# OpenVLC_1_3_2.net
KiCad netlist of a schematic drawn in Altium Designer
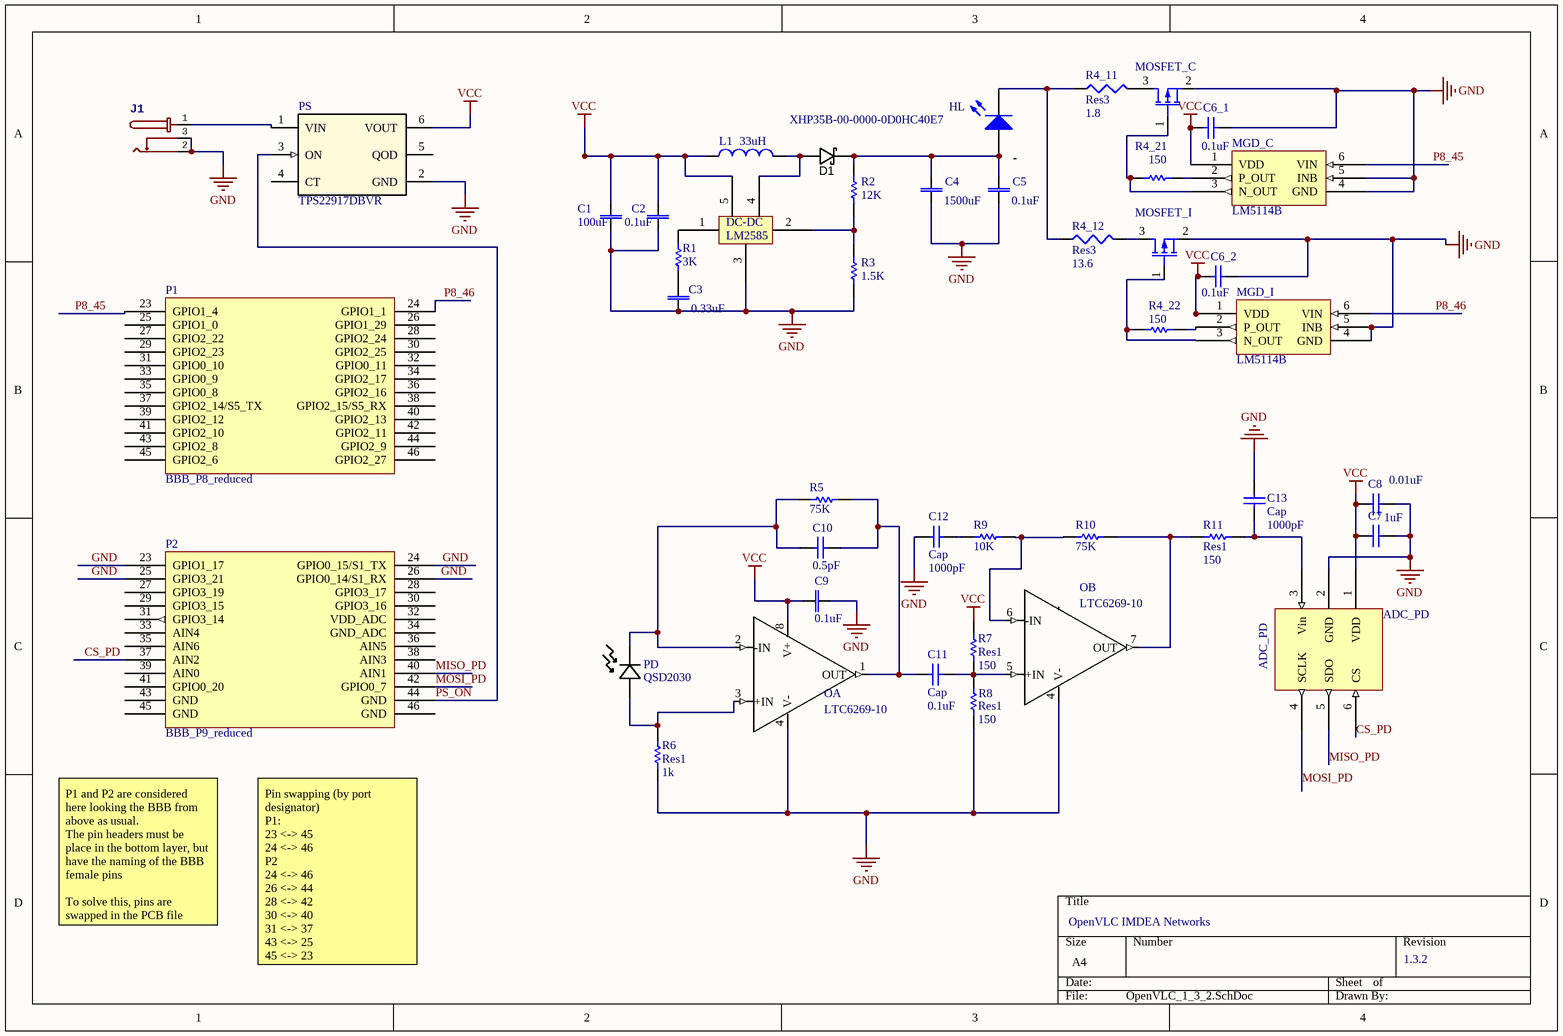
[diagram p0: OpenVLC_1_3_2.SchDoc]

(export (version "E")
  (design (tool "Eeschema 10.0.6"))
  (components
    (comp (ref "ADC_PD")
      (value "ADC_PD")
      (footprint "SOT23-6")
      (libsource (lib "BeagleBoneCape") (part "ADS7883"))
    )
    (comp (ref "C1")
      (value "100uF")
      (footprint "WCAP-ATG8 6.3x11x2.5x0.5")
      (description "Capacitor")
      (fields (field (name "Comment") "Cap") (field (name "PUBLISHER") "Altium Limited"))
      (libsource (lib "") (part "Cap_1"))
    )
    (comp (ref "C2")
      (value "0.1uF")
      (footprint "1608[0603]")
      (description "Capacitor")
      (fields (field (name "Comment") "Cap") (field (name "PUBLISHER") "Altium Limited"))
      (libsource (lib "") (part "Cap_1"))
    )
    (comp (ref "C3")
      (value "0.33uF")
      (footprint "1608[0603]")
      (description "Capacitor")
      (fields (field (name "Comment") "Cap") (field (name "PUBLISHER") "Altium Limited"))
      (libsource (lib "") (part "Cap_1"))
    )
    (comp (ref "C4")
      (value "1500uF")
      (footprint "WCAP-ATG8 10x12.5x5x0.6")
      (description "Capacitor")
      (fields (field (name "Comment") "Cap") (field (name "PUBLISHER") "Altium Limited"))
      (libsource (lib "") (part "Cap_1"))
    )
    (comp (ref "C5")
      (value "0.1uF")
      (footprint "1608[0603]")
      (description "Capacitor")
      (fields (field (name "Comment") "Cap") (field (name "PUBLISHER") "Altium Limited"))
      (libsource (lib "") (part "Cap_1"))
    )
    (comp (ref "C6_1")
      (value "0.1uF")
      (footprint "1608[0603]")
      (description "Capacitor")
      (fields (field (name "Comment") "Cap") (field (name "PUBLISHER") "Altium Limited"))
      (libsource (lib "Miscellaneous Devices") (part "Cap"))
    )
    (comp (ref "C6_2")
      (value "0.1uF")
      (footprint "1608[0603]")
      (description "Capacitor")
      (fields (field (name "Comment") "Cap") (field (name "PUBLISHER") "Altium Limited"))
      (libsource (lib "Miscellaneous Devices") (part "Cap"))
    )
    (comp (ref "C7")
      (value "1uF")
      (footprint "1608[0603]")
      (description "Capacitor")
      (fields (field (name "Comment") "Cap") (field (name "PUBLISHER") "Altium Limited"))
      (libsource (lib "Miscellaneous Devices") (part "Cap"))
    )
    (comp (ref "C8")
      (value "0.01uF")
      (footprint "1608[0603]")
      (description "Capacitor")
      (fields (field (name "Comment") "Cap") (field (name "PUBLISHER") "Altium Limited"))
      (libsource (lib "Miscellaneous Devices") (part "Cap"))
    )
    (comp (ref "C9")
      (value "0.1uF")
      (footprint "1608[0603]")
      (description "Capacitor")
      (fields (field (name "Comment") "Cap") (field (name "PUBLISHER") "Altium Limited"))
      (libsource (lib "BeagleBoneCape") (part "Cap"))
    )
    (comp (ref "C10")
      (value "0.5pF")
      (footprint "1608[0603]")
      (description "Capacitor")
      (fields (field (name "Comment") "Cap") (field (name "PUBLISHER") "Altium Limited"))
      (libsource (lib "Miscellaneous Devices") (part "Cap"))
    )
    (comp (ref "C11")
      (value "Cap")
      (footprint "1608[0603]")
      (description "Capacitor")
      (fields (field (name "ALTIUM_VALUE") "0.1uF") (field (name "PUBLISHER") "Altium Limited"))
      (libsource (lib "Miscellaneous Devices") (part "Cap"))
    )
    (comp (ref "C12")
      (value "Cap")
      (footprint "1608[0603]")
      (description "Capacitor")
      (fields (field (name "ALTIUM_VALUE") "1000pF") (field (name "PUBLISHER") "Altium Limited"))
      (libsource (lib "Miscellaneous Devices") (part "Cap"))
    )
    (comp (ref "C13")
      (value "Cap")
      (footprint "1608[0603]")
      (description "Capacitor")
      (fields (field (name "ALTIUM_VALUE") "1000pF") (field (name "PUBLISHER") "Altium Limited"))
      (libsource (lib "Miscellaneous Devices") (part "Cap"))
    )
    (comp (ref "D1")
      (value "~")
      (footprint "DO-214AC")
      (description "Diode Schottky SMD 100V 2A SMA")
      (libsource (lib "PBL - Diodes") (part "DIODE_SCHOTTKY_10MQ100NPBF"))
    )
    (comp (ref "DC-DC")
      (value "LM2585")
      (footprint "TO-263-5")
      (libsource (lib "BeagleBoneCape") (part "LM2585"))
    )
    (comp (ref "HL")
      (value "XHP35B-00-0000-0D0HC40E7")
      (footprint "LEDM345X345X226:LEDM345X345X226")
      (fields (field (name "PUBLISHER") "Altium Limited"))
      (libsource (lib "Miscellaneous Devices") (part "LED1"))
    )
    (comp (ref "J1")
      (value "2.0 mm Center Pin, 2.5 A, Right Angle, Through Hole, Tapered Pins, Dc Power Jack Connector")
      (footprint "CUI_PJ-102A")
      (fields (field (name "MF") "CUI") (field (name "MP") "PJ-102A"))
      (libsource (lib "PJ-102A") (part "PJ-102A"))
    )
    (comp (ref "L1")
      (value "33uH")
      (footprint "WCAP-ATG8:WCAP-ATG8 8x16x5x0.5")
      (description "Inductor")
      (fields (field (name "PUBLISHER") "Altium Limited"))
      (libsource (lib "Miscellaneous Devices") (part "Inductor"))
    )
    (comp (ref "MGD_C")
      (value "LM5114B")
      (footprint "SOT23-6_N")
      (description "MOSFET Gate Driver")
      (libsource (lib "BeagleBoneCape") (part "LM5114B"))
    )
    (comp (ref "MGD_I")
      (value "LM5114B")
      (footprint "SOT23-6_N")
      (description "MOSFET Gate Driver")
      (libsource (lib "BeagleBoneCape") (part "LM5114B"))
    )
    (comp (ref "MOSFET_C")
      (value "MOSFET")
      (footprint "SOT23-3")
      (description "P-Channel MOSFET")
      (fields (field (name "PUBLISHER") "Altium Limited"))
      (libsource (lib "Miscellaneous Devices") (part "MOSFET-P"))
    )
    (comp (ref "MOSFET_I")
      (value "MOSFET")
      (footprint "SOT23-3")
      (description "P-Channel MOSFET")
      (fields (field (name "PUBLISHER") "Altium Limited"))
      (libsource (lib "Miscellaneous Devices") (part "MOSFET-P"))
    )
    (comp (ref "O") (value "LTC6269-10") (footprint "SM8") (libsource (lib "") (part "LTC6269-10_1")))
    (comp (ref "P1")
      (value "BBB_P8_reduced")
      (footprint "BBB_CAPE_NO_HEADER_R_24")
      (libsource (lib "BeagleBoneCape") (part "BBB_P8_reduced"))
    )
    (comp (ref "P2")
      (value "BBB_P9_reduced")
      (footprint "BBB_CAPE_NO_HEADER_R_24")
      (libsource (lib "BeagleBoneCape") (part "BBB_P9_reduced"))
    )
    (comp (ref "PD")
      (value "QSD2030")
      (footprint "LED_T-1_34_100CF_OSI")
      (description "No Description Available")
      (libsource (lib "OpenVLC_1_3_2_SchLibrary") (part "QSD2030"))
    )
    (comp (ref "PS")
      (value "TPS22917DBVR")
      (footprint "DBV0006_N")
      (description "Power Switch 1.7-5.5V")
      (libsource (lib "Multi_OpenVLC_SchLibrary") (part "TPS22917DBVR"))
    )
    (comp (ref "R1")
      (value "3K")
      (footprint "1608[0603]")
      (description "Semiconductor Resistor")
      (fields (field (name "Comment") "Res Semi") (field (name "PUBLISHER") "Altium Limited"))
      (libsource (lib "Miscellaneous Devices") (part "Res Semi"))
    )
    (comp (ref "R2")
      (value "12K")
      (footprint "1608[0603]")
      (description "Resistor")
      (fields (field (name "Comment") "Res1") (field (name "PUBLISHER") "Altium Limited"))
      (libsource (lib "Miscellaneous Devices") (part "Res1"))
    )
    (comp (ref "R3")
      (value "1.5K")
      (footprint "1608[0603]")
      (description "Resistor")
      (fields (field (name "Comment") "Res1") (field (name "PUBLISHER") "Altium Limited"))
      (libsource (lib "Miscellaneous Devices") (part "Res1"))
    )
    (comp (ref "R4_11")
      (value "Res3")
      (footprint "14-1210")
      (description "Resistor")
      (fields (field (name "ALTIUM_VALUE") "1.8") (field (name "PUBLISHER") "Altium Limited"))
      (libsource (lib "Miscellaneous Devices") (part "Res3"))
    )
    (comp (ref "R4_12")
      (value "Res3")
      (footprint "C1206")
      (description "Resistor")
      (fields (field (name "ALTIUM_VALUE") "13.6") (field (name "PUBLISHER") "Altium Limited"))
      (libsource (lib "Miscellaneous Devices") (part "Res3"))
    )
    (comp (ref "R4_21")
      (value "150")
      (footprint "1608[0603]")
      (description "Resistor")
      (fields (field (name "Comment") "Res1") (field (name "PUBLISHER") "Altium Limited"))
      (libsource (lib "Miscellaneous Devices") (part "Res1"))
    )
    (comp (ref "R4_22")
      (value "150")
      (footprint "1608[0603]")
      (description "Resistor")
      (fields (field (name "Comment") "Res1") (field (name "PUBLISHER") "Altium Limited"))
      (libsource (lib "Miscellaneous Devices") (part "Res1"))
    )
    (comp (ref "R5")
      (value "75K")
      (footprint "1608[0603]")
      (description "Resistor")
      (fields (field (name "Comment") "Res1") (field (name "PUBLISHER") "Altium Limited"))
      (libsource (lib "Miscellaneous Devices") (part "Res1"))
    )
    (comp (ref "R6")
      (value "Res1")
      (footprint "1608[0603]")
      (description "Resistor")
      (fields (field (name "ALTIUM_VALUE") "1k") (field (name "PUBLISHER") "Altium Limited"))
      (libsource (lib "Miscellaneous Devices") (part "Res1"))
    )
    (comp (ref "R7")
      (value "Res1")
      (footprint "Miscellaneous Devices:1608[0603]")
      (description "Resistor")
      (fields (field (name "ALTIUM_VALUE") "150") (field (name "PUBLISHER") "Altium Limited"))
      (libsource (lib "Miscellaneous Devices") (part "Res1"))
    )
    (comp (ref "R8")
      (value "Res1")
      (footprint "1608[0603]")
      (description "Resistor")
      (fields (field (name "ALTIUM_VALUE") "150") (field (name "PUBLISHER") "Altium Limited"))
      (libsource (lib "Miscellaneous Devices") (part "Res1"))
    )
    (comp (ref "R9")
      (value "10K")
      (footprint "1608[0603]")
      (description "Resistor")
      (fields (field (name "Comment") "Res1") (field (name "PUBLISHER") "Altium Limited"))
      (libsource (lib "Miscellaneous Devices") (part "Res1"))
    )
    (comp (ref "R10")
      (value "75K")
      (footprint "1608[0603]")
      (description "Resistor")
      (fields (field (name "Comment") "Res1") (field (name "PUBLISHER") "Altium Limited"))
      (libsource (lib "Miscellaneous Devices") (part "Res1"))
    )
    (comp (ref "R11")
      (value "Res1")
      (footprint "1608[0603]")
      (description "Resistor")
      (fields (field (name "ALTIUM_VALUE") "150") (field (name "PUBLISHER") "Altium Limited"))
      (libsource (lib "Miscellaneous Devices") (part "Res1"))
    )
  )
  (nets
    (net (code "1") (name "/CS_PD") (class "Default")
      (node (ref "ADC_PD") (pin "6") (pinfunction "CS_6") (pintype "input"))
      (node (ref "P2") (pin "37") (pinfunction "AIN2_37") (pintype "passive"))
    )
    (net (code "2") (name "/MISO_PD") (class "Default")
      (node (ref "ADC_PD") (pin "5") (pinfunction "SDO_5") (pintype "output"))
      (node (ref "P2") (pin "40") (pinfunction "AIN1_40") (pintype "passive"))
    )
    (net (code "3") (name "/MOSI_PD") (class "Default")
      (node (ref "ADC_PD") (pin "4") (pinfunction "SCLK_4") (pintype "output"))
      (node (ref "P2") (pin "42") (pinfunction "GPIO0_7_42") (pintype "passive"))
    )
    (net (code "4") (name "/P8_45") (class "Default")
      (node (ref "MGD_C") (pin "6") (pinfunction "VIN_6") (pintype "input"))
      (node (ref "P1") (pin "23") (pinfunction "GPIO1_4_23") (pintype "passive"))
    )
    (net (code "5") (name "/P8_46") (class "Default")
      (node (ref "MGD_I") (pin "6") (pinfunction "VIN_6") (pintype "input"))
      (node (ref "P1") (pin "24") (pinfunction "GPIO1_1_24") (pintype "passive"))
    )
    (net (code "6") (name "/PS_ON") (class "Default")
      (node (ref "P2") (pin "44") (pinfunction "GND_44") (pintype "passive"))
      (node (ref "PS") (pin "3") (pinfunction "ON_3") (pintype "input"))
    )
    (net (code "7") (name "GND") (class "Default")
      (node (ref "ADC_PD") (pin "2") (pinfunction "GND_2") (pintype "power_in"))
      (node (ref "C1") (pin "2") (pinfunction "2_2") (pintype "passive"))
      (node (ref "C12") (pin "1") (pinfunction "1_1") (pintype "passive"))
      (node (ref "C13") (pin "2") (pinfunction "2_2") (pintype "passive"))
      (node (ref "C2") (pin "2") (pinfunction "2_2") (pintype "passive"))
      (node (ref "C3") (pin "2") (pinfunction "2_2") (pintype "passive"))
      (node (ref "C4") (pin "2") (pinfunction "2_2") (pintype "passive"))
      (node (ref "C5") (pin "2") (pinfunction "2_2") (pintype "passive"))
      (node (ref "C6_1") (pin "2") (pinfunction "2_2") (pintype "passive"))
      (node (ref "C6_2") (pin "2") (pinfunction "2_2") (pintype "passive"))
      (node (ref "C7") (pin "2") (pinfunction "2_2") (pintype "passive"))
      (node (ref "C8") (pin "2") (pinfunction "2_2") (pintype "passive"))
      (node (ref "C9") (pin "1") (pinfunction "1_1") (pintype "passive"))
      (node (ref "DC-DC") (pin "3") (pinfunction "GND_3") (pintype "passive"))
      (node (ref "J1") (pin "2") (pinfunction "2_2") (pintype "power_in"))
      (node (ref "J1") (pin "3") (pinfunction "3_3") (pintype "power_in"))
      (node (ref "MGD_C") (pin "4") (pinfunction "GND_4") (pintype "power_in"))
      (node (ref "MGD_C") (pin "5") (pinfunction "INB_5") (pintype "input"))
      (node (ref "MGD_I") (pin "4") (pinfunction "GND_4") (pintype "power_in"))
      (node (ref "MGD_I") (pin "5") (pinfunction "INB_5") (pintype "input"))
      (node (ref "MOSFET_C") (pin "2") (pinfunction "S_2") (pintype "passive"))
      (node (ref "MOSFET_I") (pin "2") (pinfunction "S_2") (pintype "passive"))
      (node (ref "O") (pin "4") (pinfunction "V-_4") (pintype "power_in"))
      (node (ref "P2") (pin "23") (pinfunction "GPIO1_17_23") (pintype "passive"))
      (node (ref "P2") (pin "24") (pinfunction "GPIO0_15/S1_TX_24") (pintype "passive"))
      (node (ref "P2") (pin "25") (pinfunction "GPIO3_21_25") (pintype "passive"))
      (node (ref "P2") (pin "26") (pinfunction "GPIO0_14/S1_RX_26") (pintype "passive"))
      (node (ref "PS") (pin "2") (pinfunction "GND_2") (pintype "power_in"))
      (node (ref "R3") (pin "1") (pinfunction "1_1") (pintype "passive"))
      (node (ref "R6") (pin "1") (pinfunction "1_1") (pintype "passive"))
      (node (ref "R8") (pin "1") (pinfunction "1_1") (pintype "passive"))
    )
    (net (code "8") (name "Net-(ADC_PD-Vin)") (class "Default")
      (node (ref "ADC_PD") (pin "3") (pinfunction "Vin_3") (pintype "input"))
      (node (ref "C13") (pin "1") (pinfunction "1_1") (pintype "passive"))
      (node (ref "R11") (pin "1") (pinfunction "1_1") (pintype "passive"))
    )
    (net (code "9") (name "Net-(C3-Pad1)") (class "Default")
      (node (ref "C3") (pin "1") (pinfunction "1_1") (pintype "passive"))
      (node (ref "R1") (pin "1") (pinfunction "1_1") (pintype "passive"))
    )
    (net (code "10") (name "Net-(C12-Pad2)") (class "Default")
      (node (ref "C12") (pin "2") (pinfunction "2_2") (pintype "passive"))
      (node (ref "R9") (pin "2") (pinfunction "2_2") (pintype "passive"))
    )
    (net (code "11") (name "Net-(DC-DC-Comp)") (class "Default")
      (node (ref "DC-DC") (pin "1") (pinfunction "Comp_1") (pintype "passive"))
      (node (ref "R1") (pin "2") (pinfunction "2_2") (pintype "passive"))
    )
    (net (code "12") (name "Net-(DC-DC-Feedack)") (class "Default")
      (node (ref "DC-DC") (pin "2") (pinfunction "Feedack_2") (pintype "passive"))
      (node (ref "R2") (pin "1") (pinfunction "1_1") (pintype "passive"))
      (node (ref "R3") (pin "2") (pinfunction "2_2") (pintype "passive"))
    )
    (net (code "13") (name "Net-(DC-DC-Switch)") (class "Default")
      (node (ref "D1") (pin "A") (pinfunction "A_A") (pintype "passive"))
      (node (ref "DC-DC") (pin "4") (pinfunction "Switch_4") (pintype "passive"))
      (node (ref "L1") (pin "2") (pinfunction "2_2") (pintype "passive"))
    )
    (net (code "14") (name "Net-(HL-A)") (class "Default")
      (node (ref "C4") (pin "1") (pinfunction "1_1") (pintype "passive"))
      (node (ref "C5") (pin "1") (pinfunction "1_1") (pintype "passive"))
      (node (ref "D1") (pin "K") (pinfunction "K_K") (pintype "passive"))
      (node (ref "HL") (pin "1") (pinfunction "A_1") (pintype "passive"))
      (node (ref "R2") (pin "2") (pinfunction "2_2") (pintype "passive"))
    )
    (net (code "15") (name "Net-(HL-K)") (class "Default")
      (node (ref "HL") (pin "2") (pinfunction "K_2") (pintype "passive"))
      (node (ref "R4_11") (pin "1") (pinfunction "1_1") (pintype "passive"))
      (node (ref "R4_12") (pin "1") (pinfunction "1_1") (pintype "passive"))
    )
    (net (code "16") (name "Net-(MGD_C-N_OUT)") (class "Default")
      (node (ref "MGD_C") (pin "3") (pinfunction "N_OUT_3") (pintype "output"))
      (node (ref "MOSFET_C") (pin "1") (pinfunction "G_1") (pintype "passive"))
      (node (ref "R4_21") (pin "1") (pinfunction "1_1") (pintype "passive"))
    )
    (net (code "17") (name "Net-(MGD_C-P_OUT)") (class "Default")
      (node (ref "MGD_C") (pin "2") (pinfunction "P_OUT_2") (pintype "output"))
      (node (ref "R4_21") (pin "2") (pinfunction "2_2") (pintype "passive"))
    )
    (net (code "18") (name "Net-(MGD_I-N_OUT)") (class "Default")
      (node (ref "MGD_I") (pin "3") (pinfunction "N_OUT_3") (pintype "output"))
      (node (ref "MOSFET_I") (pin "1") (pinfunction "G_1") (pintype "passive"))
      (node (ref "R4_22") (pin "1") (pinfunction "1_1") (pintype "passive"))
    )
    (net (code "19") (name "Net-(MGD_I-P_OUT)") (class "Default")
      (node (ref "MGD_I") (pin "2") (pinfunction "P_OUT_2") (pintype "output"))
      (node (ref "R4_22") (pin "2") (pinfunction "2_2") (pintype "passive"))
    )
    (net (code "20") (name "Net-(MOSFET_C-D)") (class "Default")
      (node (ref "MOSFET_C") (pin "3") (pinfunction "D_3") (pintype "passive"))
      (node (ref "R4_11") (pin "2") (pinfunction "2_2") (pintype "passive"))
    )
    (net (code "21") (name "Net-(MOSFET_I-D)") (class "Default")
      (node (ref "MOSFET_I") (pin "3") (pinfunction "D_3") (pintype "passive"))
      (node (ref "R4_12") (pin "2") (pinfunction "2_2") (pintype "passive"))
    )
    (net (code "22") (name "Net-(OA-+IN)") (class "Default")
      (node (ref "O") (pin "3") (pinfunction "+IN_3") (pintype "input"))
      (node (ref "PD") (pin "2") (pinfunction "ANODE_2") (pintype "passive"))
      (node (ref "R6") (pin "2") (pinfunction "2_2") (pintype "passive"))
    )
    (net (code "23") (name "Net-(OA--IN)") (class "Default")
      (node (ref "C10") (pin "1") (pinfunction "1_1") (pintype "passive"))
      (node (ref "O") (pin "2") (pinfunction "-IN_2") (pintype "input"))
      (node (ref "PD") (pin "1") (pinfunction "CATHODE_1") (pintype "passive"))
      (node (ref "R5") (pin "1") (pinfunction "1_1") (pintype "passive"))
    )
    (net (code "24") (name "Net-(OA-OUT)") (class "Default")
      (node (ref "C10") (pin "2") (pinfunction "2_2") (pintype "passive"))
      (node (ref "C11") (pin "1") (pinfunction "1_1") (pintype "passive"))
      (node (ref "O") (pin "1") (pinfunction "OUT_1") (pintype "output"))
      (node (ref "R5") (pin "2") (pinfunction "2_2") (pintype "passive"))
    )
    (net (code "25") (name "Net-(OB-+IN)") (class "Default")
      (node (ref "C11") (pin "2") (pinfunction "2_2") (pintype "passive"))
      (node (ref "O") (pin "5") (pinfunction "+IN_5") (pintype "input"))
      (node (ref "R7") (pin "1") (pinfunction "1_1") (pintype "passive"))
      (node (ref "R8") (pin "2") (pinfunction "2_2") (pintype "passive"))
    )
    (net (code "26") (name "Net-(OB--IN)") (class "Default")
      (node (ref "O") (pin "6") (pinfunction "-IN_6") (pintype "input"))
      (node (ref "R10") (pin "2") (pinfunction "2_2") (pintype "passive"))
      (node (ref "R9") (pin "1") (pinfunction "1_1") (pintype "passive"))
    )
    (net (code "27") (name "Net-(OB-OUT)") (class "Default")
      (node (ref "O") (pin "7") (pinfunction "OUT_7") (pintype "output"))
      (node (ref "R10") (pin "1") (pinfunction "1_1") (pintype "passive"))
      (node (ref "R11") (pin "2") (pinfunction "2_2") (pintype "passive"))
    )
    (net (code "28") (name "Net-(PS-VIN)") (class "Default")
      (node (ref "J1") (pin "1") (pinfunction "1_1") (pintype "power_in"))
      (node (ref "PS") (pin "1") (pinfunction "VIN_1") (pintype "power_in"))
    )
    (net (code "29") (name "VCC") (class "Default")
      (node (ref "ADC_PD") (pin "1") (pinfunction "VDD_1") (pintype "power_in"))
      (node (ref "C1") (pin "1") (pinfunction "1_1") (pintype "passive"))
      (node (ref "C2") (pin "1") (pinfunction "1_1") (pintype "passive"))
      (node (ref "C6_1") (pin "1") (pinfunction "1_1") (pintype "passive"))
      (node (ref "C6_2") (pin "1") (pinfunction "1_1") (pintype "passive"))
      (node (ref "C7") (pin "1") (pinfunction "1_1") (pintype "passive"))
      (node (ref "C8") (pin "1") (pinfunction "1_1") (pintype "passive"))
      (node (ref "C9") (pin "2") (pinfunction "2_2") (pintype "passive"))
      (node (ref "DC-DC") (pin "5") (pinfunction "Vin_5") (pintype "passive"))
      (node (ref "L1") (pin "1") (pinfunction "1_1") (pintype "passive"))
      (node (ref "MGD_C") (pin "1") (pinfunction "VDD_1") (pintype "power_in"))
      (node (ref "MGD_I") (pin "1") (pinfunction "VDD_1") (pintype "power_in"))
      (node (ref "O") (pin "8") (pinfunction "V+_8") (pintype "power_in"))
      (node (ref "PS") (pin "6") (pinfunction "VOUT_6") (pintype "power_in"))
      (node (ref "R7") (pin "2") (pinfunction "2_2") (pintype "passive"))
    )
    (net (code "30") (name "unconnected-(HL-Thermal-Pad3)") (class "Default")
      (node (ref "HL") (pin "3") (pinfunction "Thermal_3") (pintype "passive"))
    )
    (net (code "31") (name "unconnected-(P1-GPIO0_8-Pad35)") (class "Default")
      (node (ref "P1") (pin "35") (pinfunction "GPIO0_8_35") (pintype "passive"))
    )
    (net (code "32") (name "unconnected-(P1-GPIO0_9-Pad33)") (class "Default")
      (node (ref "P1") (pin "33") (pinfunction "GPIO0_9_33") (pintype "passive"))
    )
    (net (code "33") (name "unconnected-(P1-GPIO0_10-Pad31)") (class "Default")
      (node (ref "P1") (pin "31") (pinfunction "GPIO0_10_31") (pintype "passive"))
    )
    (net (code "34") (name "unconnected-(P1-GPIO0_11-Pad32)") (class "Default")
      (node (ref "P1") (pin "32") (pinfunction "GPIO0_11_32") (pintype "passive"))
    )
    (net (code "35") (name "unconnected-(P1-GPIO1_0-Pad25)") (class "Default")
      (node (ref "P1") (pin "25") (pinfunction "GPIO1_0_25") (pintype "passive"))
    )
    (net (code "36") (name "unconnected-(P1-GPIO1_29-Pad26)") (class "Default")
      (node (ref "P1") (pin "26") (pinfunction "GPIO1_29_26") (pintype "passive"))
    )
    (net (code "37") (name "unconnected-(P1-GPIO2_6-Pad45)") (class "Default")
      (node (ref "P1") (pin "45") (pinfunction "GPIO2_6_45") (pintype "passive"))
    )
    (net (code "38") (name "unconnected-(P1-GPIO2_8-Pad43)") (class "Default")
      (node (ref "P1") (pin "43") (pinfunction "GPIO2_8_43") (pintype "passive"))
    )
    (net (code "39") (name "unconnected-(P1-GPIO2_9-Pad44)") (class "Default")
      (node (ref "P1") (pin "44") (pinfunction "GPIO2_9_44") (pintype "passive"))
    )
    (net (code "40") (name "unconnected-(P1-GPIO2_10-Pad41)") (class "Default")
      (node (ref "P1") (pin "41") (pinfunction "GPIO2_10_41") (pintype "passive"))
    )
    (net (code "41") (name "unconnected-(P1-GPIO2_11-Pad42)") (class "Default")
      (node (ref "P1") (pin "42") (pinfunction "GPIO2_11_42") (pintype "passive"))
    )
    (net (code "42") (name "unconnected-(P1-GPIO2_12-Pad39)") (class "Default")
      (node (ref "P1") (pin "39") (pinfunction "GPIO2_12_39") (pintype "passive"))
    )
    (net (code "43") (name "unconnected-(P1-GPIO2_13-Pad40)") (class "Default")
      (node (ref "P1") (pin "40") (pinfunction "GPIO2_13_40") (pintype "passive"))
    )
    (net (code "44") (name "unconnected-(P1-GPIO2_14{slash}S5_TX-Pad37)") (class "Default")
      (node (ref "P1") (pin "37") (pinfunction "GPIO2_14/S5_TX_37") (pintype "passive"))
    )
    (net (code "45") (name "unconnected-(P1-GPIO2_15{slash}S5_RX-Pad38)") (class "Default")
      (node (ref "P1") (pin "38") (pinfunction "GPIO2_15/S5_RX_38") (pintype "passive"))
    )
    (net (code "46") (name "unconnected-(P1-GPIO2_16-Pad36)") (class "Default")
      (node (ref "P1") (pin "36") (pinfunction "GPIO2_16_36") (pintype "passive"))
    )
    (net (code "47") (name "unconnected-(P1-GPIO2_17-Pad34)") (class "Default")
      (node (ref "P1") (pin "34") (pinfunction "GPIO2_17_34") (pintype "passive"))
    )
    (net (code "48") (name "unconnected-(P1-GPIO2_22-Pad27)") (class "Default")
      (node (ref "P1") (pin "27") (pinfunction "GPIO2_22_27") (pintype "passive"))
    )
    (net (code "49") (name "unconnected-(P1-GPIO2_23-Pad29)") (class "Default")
      (node (ref "P1") (pin "29") (pinfunction "GPIO2_23_29") (pintype "passive"))
    )
    (net (code "50") (name "unconnected-(P1-GPIO2_24-Pad28)") (class "Default")
      (node (ref "P1") (pin "28") (pinfunction "GPIO2_24_28") (pintype "passive"))
    )
    (net (code "51") (name "unconnected-(P1-GPIO2_25-Pad30)") (class "Default")
      (node (ref "P1") (pin "30") (pinfunction "GPIO2_25_30") (pintype "passive"))
    )
    (net (code "52") (name "unconnected-(P1-GPIO2_27-Pad46)") (class "Default")
      (node (ref "P1") (pin "46") (pinfunction "GPIO2_27_46") (pintype "passive"))
    )
    (net (code "53") (name "unconnected-(P2-AIN0-Pad39)") (class "Default")
      (node (ref "P2") (pin "39") (pinfunction "AIN0_39") (pintype "passive"))
    )
    (net (code "54") (name "unconnected-(P2-AIN3-Pad38)") (class "Default")
      (node (ref "P2") (pin "38") (pinfunction "AIN3_38") (pintype "passive"))
    )
    (net (code "55") (name "unconnected-(P2-AIN4-Pad33)") (class "Default")
      (node (ref "P2") (pin "33") (pinfunction "AIN4_33") (pintype "passive"))
    )
    (net (code "56") (name "unconnected-(P2-AIN5-Pad36)") (class "Default")
      (node (ref "P2") (pin "36") (pinfunction "AIN5_36") (pintype "passive"))
    )
    (net (code "57") (name "unconnected-(P2-AIN6-Pad35)") (class "Default")
      (node (ref "P2") (pin "35") (pinfunction "AIN6_35") (pintype "passive"))
    )
    (net (code "58") (name "unconnected-(P2-GND-Pad43)") (class "Default")
      (node (ref "P2") (pin "43") (pinfunction "GND_43") (pintype "passive"))
    )
    (net (code "59") (name "unconnected-(P2-GND-Pad45)") (class "Default")
      (node (ref "P2") (pin "45") (pinfunction "GND_45") (pintype "passive"))
    )
    (net (code "60") (name "unconnected-(P2-GND-Pad46)") (class "Default")
      (node (ref "P2") (pin "46") (pinfunction "GND_46") (pintype "passive"))
    )
    (net (code "61") (name "unconnected-(P2-GND_ADC-Pad34)") (class "Default")
      (node (ref "P2") (pin "34") (pinfunction "GND_ADC_34") (pintype "passive"))
    )
    (net (code "62") (name "unconnected-(P2-GPIO0_20-Pad41)") (class "Default")
      (node (ref "P2") (pin "41") (pinfunction "GPIO0_20_41") (pintype "passive"))
    )
    (net (code "63") (name "unconnected-(P2-GPIO3_14-Pad31)") (class "Default")
      (node (ref "P2") (pin "31") (pinfunction "GPIO3_14_31") (pintype "output"))
    )
    (net (code "64") (name "unconnected-(P2-GPIO3_15-Pad29)") (class "Default")
      (node (ref "P2") (pin "29") (pinfunction "GPIO3_15_29") (pintype "passive"))
    )
    (net (code "65") (name "unconnected-(P2-GPIO3_16-Pad30)") (class "Default")
      (node (ref "P2") (pin "30") (pinfunction "GPIO3_16_30") (pintype "passive"))
    )
    (net (code "66") (name "unconnected-(P2-GPIO3_17-Pad28)") (class "Default")
      (node (ref "P2") (pin "28") (pinfunction "GPIO3_17_28") (pintype "passive"))
    )
    (net (code "67") (name "unconnected-(P2-GPIO3_19-Pad27)") (class "Default")
      (node (ref "P2") (pin "27") (pinfunction "GPIO3_19_27") (pintype "passive"))
    )
    (net (code "68") (name "unconnected-(P2-VDD_ADC-Pad32)") (class "Default")
      (node (ref "P2") (pin "32") (pinfunction "VDD_ADC_32") (pintype "passive"))
    )
    (net (code "69") (name "unconnected-(PS-CT-Pad4)") (class "Default")
      (node (ref "PS") (pin "4") (pinfunction "CT_4") (pintype "passive"))
    )
    (net (code "70") (name "unconnected-(PS-QOD-Pad5)") (class "Default")
      (node (ref "PS") (pin "5") (pinfunction "QOD_5") (pintype "passive"))
    )
  )
)
